# Charger_Board_2.net
KiCad netlist of a schematic drawn in EAGLE
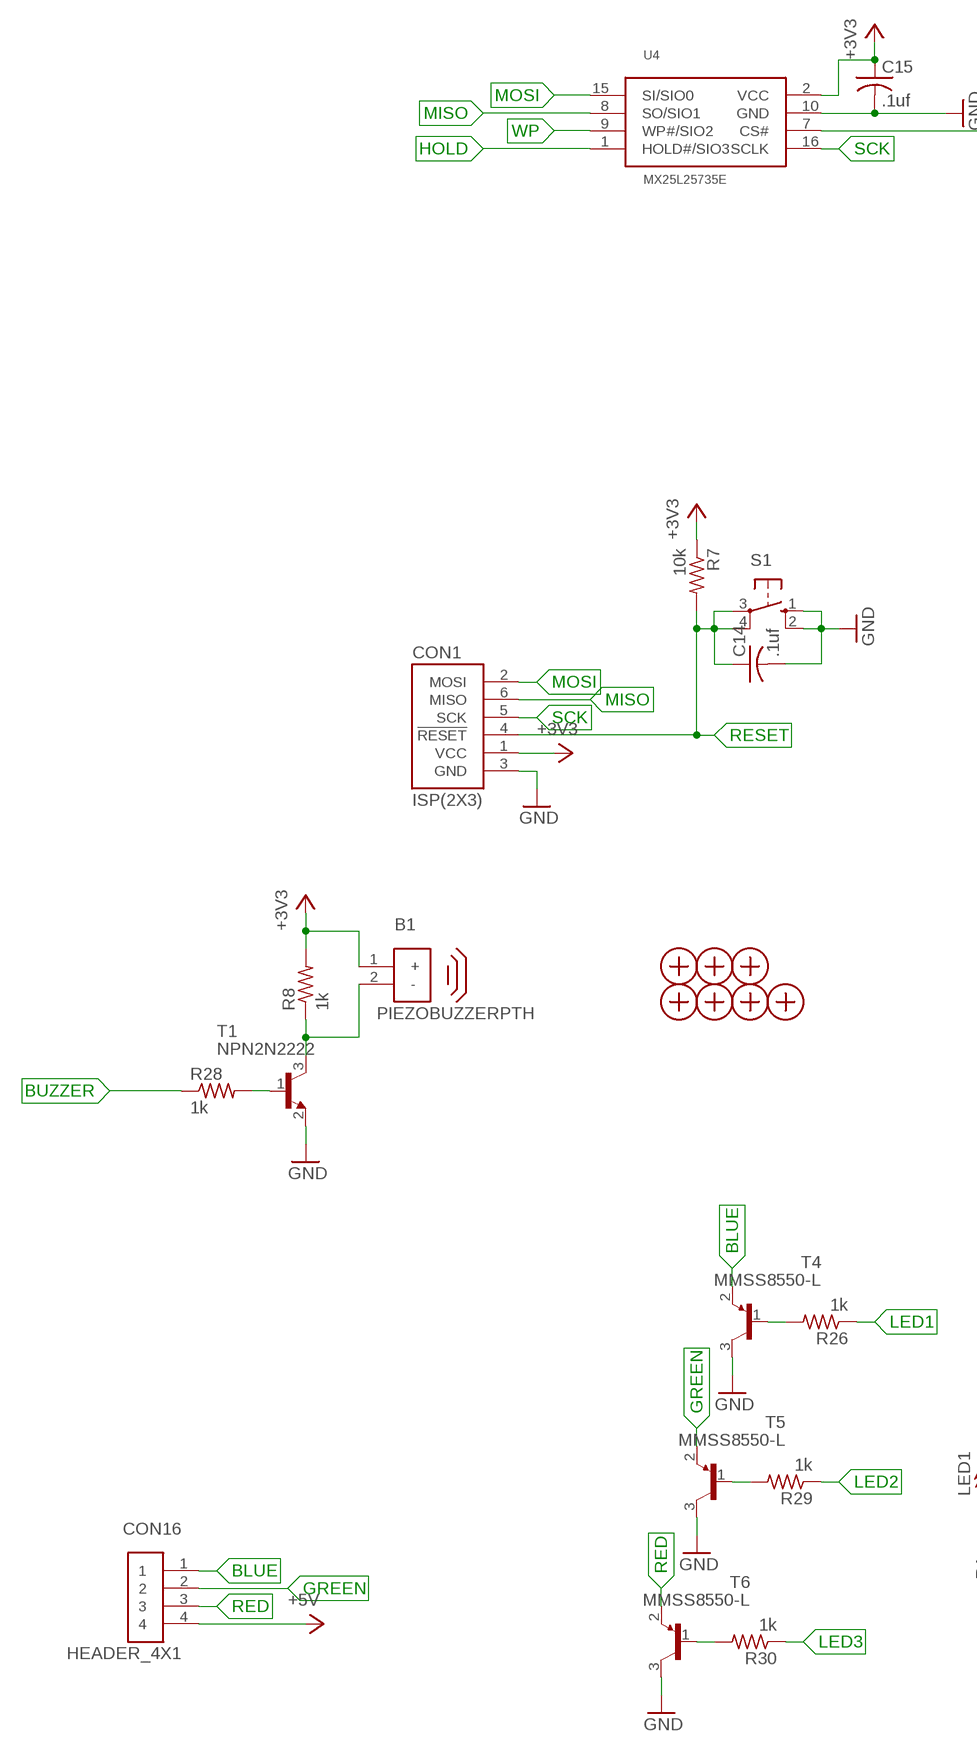
[diagram p0: schematic, sheet 1, part 1 of 2]
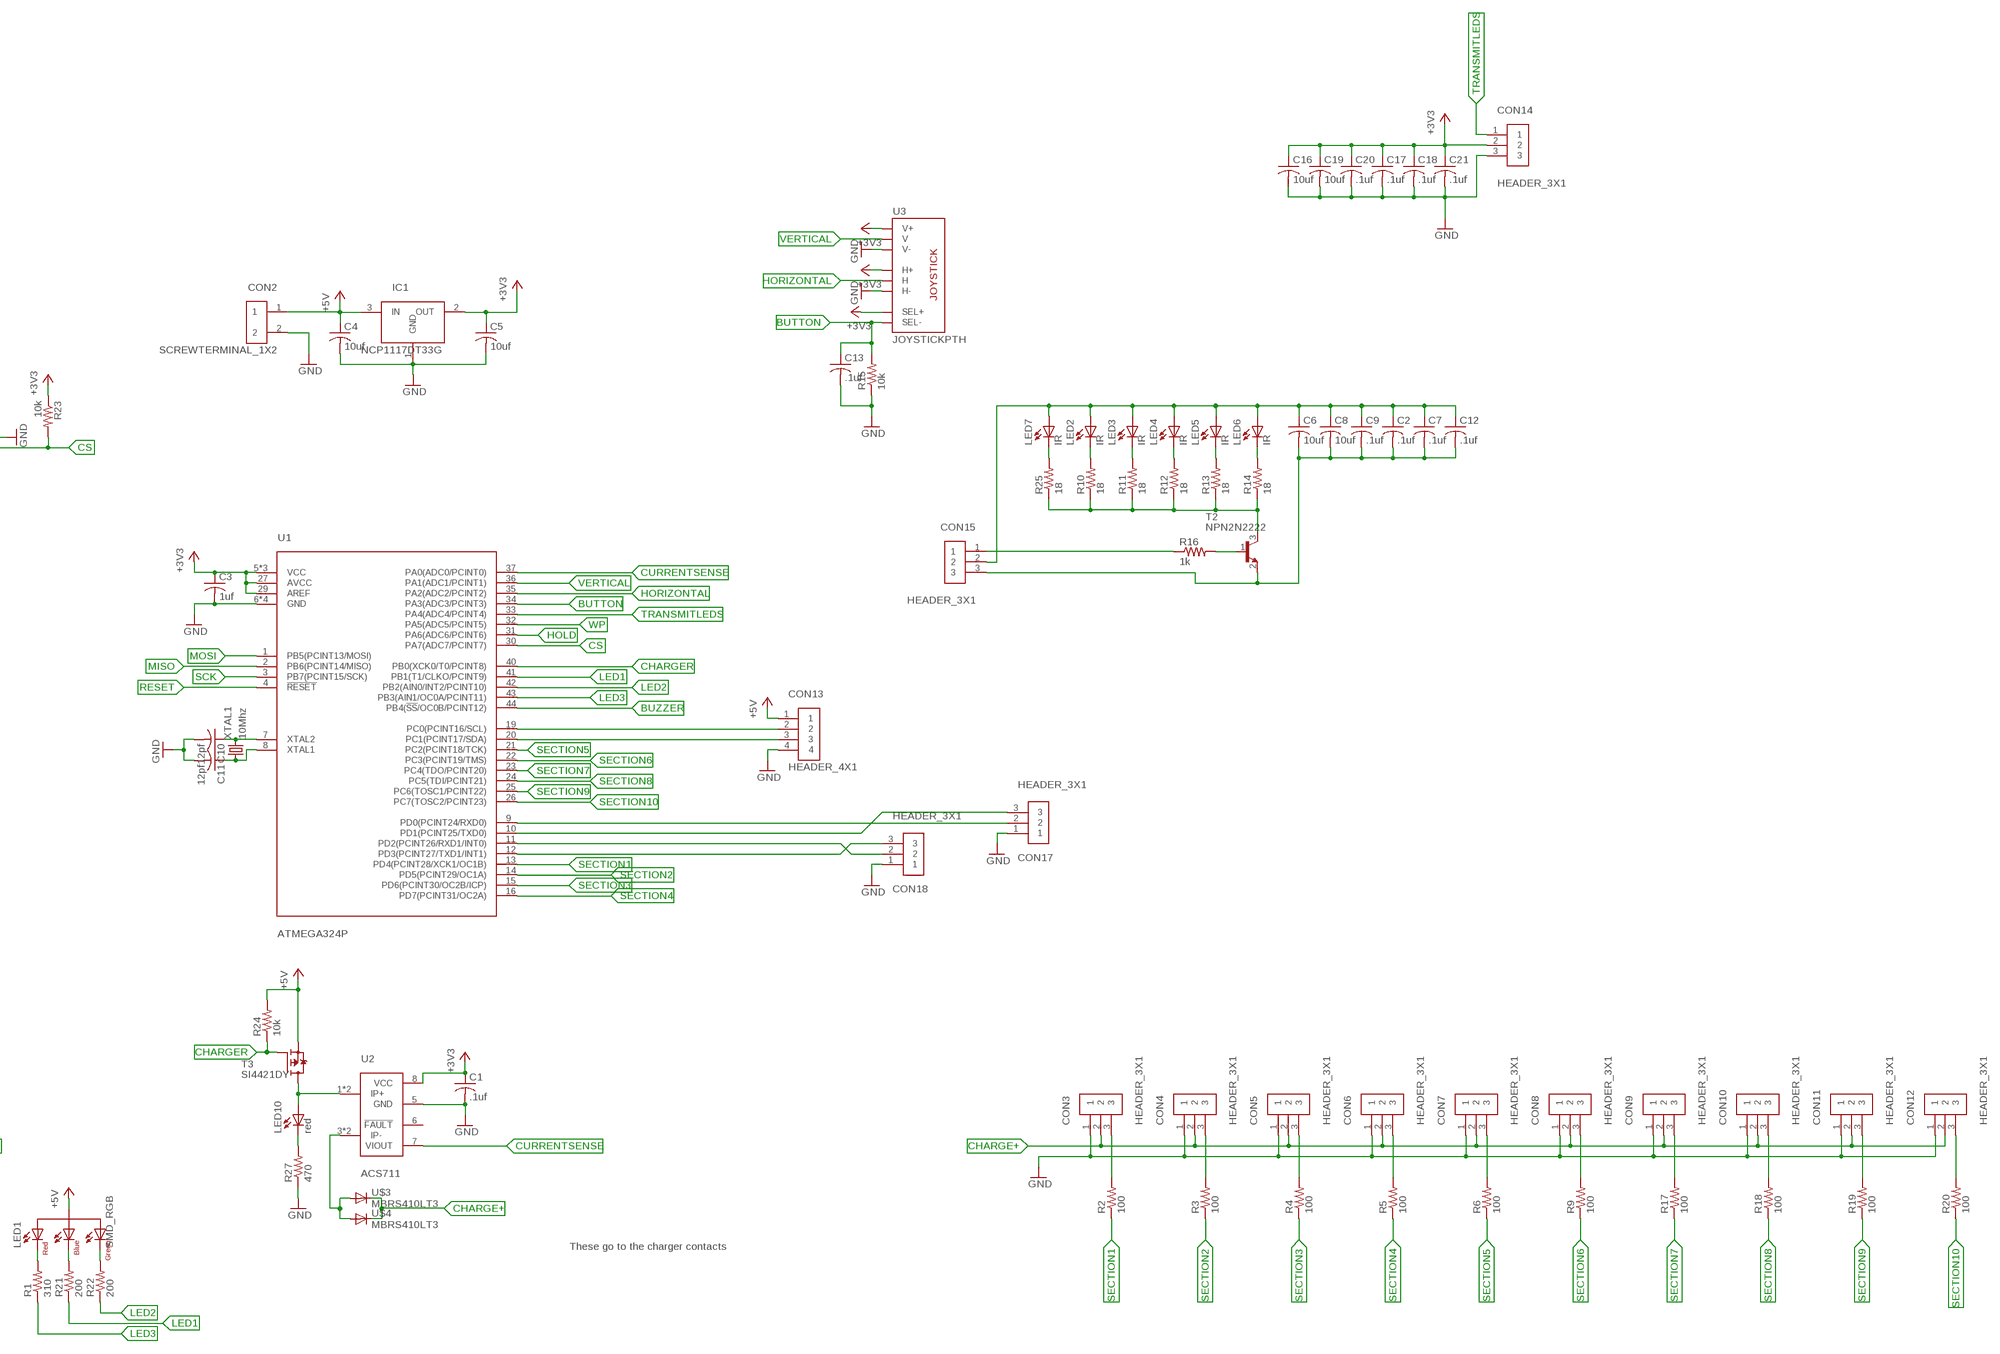
[diagram p1: schematic, sheet 1, part 2 of 2]

(export (version "E")
  (design (tool "Eeschema 10.0.6"))
  (components
    (comp (ref "B1")
      (value "PIEZOBUZZERPTH")
      (footprint "eagle-import:PIEZOBUZZER")
      (libsource (lib "eagle-import") (part "PIEZOBUZZERPTH"))
    )
    (comp (ref "C1")
      (value ".1uf")
      (footprint "eagle-import:0603")
      (libsource (lib "eagle-import") (part "CAP0603"))
    )
    (comp (ref "C2")
      (value ".1uf")
      (footprint "eagle-import:0603")
      (libsource (lib "eagle-import") (part "CAP0603"))
    )
    (comp (ref "C3")
      (value "1uf")
      (footprint "eagle-import:0603")
      (libsource (lib "eagle-import") (part "CAP0603"))
    )
    (comp (ref "C4")
      (value "10uf")
      (footprint "eagle-import:0805")
      (libsource (lib "eagle-import") (part "CAP0805"))
    )
    (comp (ref "C5")
      (value "10uf")
      (footprint "eagle-import:0805")
      (libsource (lib "eagle-import") (part "CAP0805"))
    )
    (comp (ref "C6")
      (value "10uf")
      (footprint "eagle-import:0805")
      (libsource (lib "eagle-import") (part "CAP0805"))
    )
    (comp (ref "C7")
      (value ".1uf")
      (footprint "eagle-import:0603")
      (libsource (lib "eagle-import") (part "CAP0603"))
    )
    (comp (ref "C8")
      (value "10uf")
      (footprint "eagle-import:0805")
      (libsource (lib "eagle-import") (part "CAP0805"))
    )
    (comp (ref "C9")
      (value ".1uf")
      (footprint "eagle-import:0603")
      (libsource (lib "eagle-import") (part "CAP0603"))
    )
    (comp (ref "C10")
      (value "12pf")
      (footprint "eagle-import:0603")
      (libsource (lib "eagle-import") (part "CAP0603"))
    )
    (comp (ref "C11")
      (value "12pf")
      (footprint "eagle-import:0603")
      (libsource (lib "eagle-import") (part "CAP0603"))
    )
    (comp (ref "C12")
      (value ".1uf")
      (footprint "eagle-import:0603")
      (libsource (lib "eagle-import") (part "CAP0603"))
    )
    (comp (ref "C13")
      (value ".1uf")
      (footprint "eagle-import:0603")
      (libsource (lib "eagle-import") (part "CAP0603"))
    )
    (comp (ref "C14")
      (value ".1uf")
      (footprint "eagle-import:0603")
      (libsource (lib "eagle-import") (part "CAP0603"))
    )
    (comp (ref "C15")
      (value ".1uf")
      (footprint "eagle-import:0603")
      (libsource (lib "eagle-import") (part "CAP0603"))
    )
    (comp (ref "C16")
      (value "10uf")
      (footprint "eagle-import:0805")
      (libsource (lib "eagle-import") (part "CAP0805"))
    )
    (comp (ref "C17")
      (value ".1uf")
      (footprint "eagle-import:0603")
      (libsource (lib "eagle-import") (part "CAP0603"))
    )
    (comp (ref "C18")
      (value ".1uf")
      (footprint "eagle-import:0603")
      (libsource (lib "eagle-import") (part "CAP0603"))
    )
    (comp (ref "C19")
      (value "10uf")
      (footprint "eagle-import:0805")
      (libsource (lib "eagle-import") (part "CAP0805"))
    )
    (comp (ref "C20")
      (value ".1uf")
      (footprint "eagle-import:0603")
      (libsource (lib "eagle-import") (part "CAP0603"))
    )
    (comp (ref "C21")
      (value ".1uf")
      (footprint "eagle-import:0603")
      (libsource (lib "eagle-import") (part "CAP0603"))
    )
    (comp (ref "CON1")
      (value "ISP(2X3)")
      (footprint "eagle-import:PINHEADER(2X3)")
      (libsource (lib "eagle-import") (part "ISP(2X3)"))
    )
    (comp (ref "CON2")
      (value "SCREWTERMINAL_1X2")
      (footprint "eagle-import:SCREWTERMINAL_1X2")
      (libsource (lib "eagle-import") (part "SCREWTERMINAL_1X2"))
    )
    (comp (ref "CON3")
      (value "HEADER_3X1")
      (footprint "eagle-import:3PINHEADER_.100_")
      (libsource (lib "eagle-import") (part "HEADER_3X1"))
    )
    (comp (ref "CON4")
      (value "HEADER_3X1")
      (footprint "eagle-import:3PINHEADER_.100_")
      (libsource (lib "eagle-import") (part "HEADER_3X1"))
    )
    (comp (ref "CON5")
      (value "HEADER_3X1")
      (footprint "eagle-import:3PINHEADER_.100_")
      (libsource (lib "eagle-import") (part "HEADER_3X1"))
    )
    (comp (ref "CON6")
      (value "HEADER_3X1")
      (footprint "eagle-import:3PINHEADER_.100_")
      (libsource (lib "eagle-import") (part "HEADER_3X1"))
    )
    (comp (ref "CON7")
      (value "HEADER_3X1")
      (footprint "eagle-import:3PINHEADER_.100_")
      (libsource (lib "eagle-import") (part "HEADER_3X1"))
    )
    (comp (ref "CON8")
      (value "HEADER_3X1")
      (footprint "eagle-import:3PINHEADER_.100_")
      (libsource (lib "eagle-import") (part "HEADER_3X1"))
    )
    (comp (ref "CON9")
      (value "HEADER_3X1")
      (footprint "eagle-import:3PINHEADER_.100_")
      (libsource (lib "eagle-import") (part "HEADER_3X1"))
    )
    (comp (ref "CON10")
      (value "HEADER_3X1")
      (footprint "eagle-import:3PINHEADER_.100_")
      (libsource (lib "eagle-import") (part "HEADER_3X1"))
    )
    (comp (ref "CON11")
      (value "HEADER_3X1")
      (footprint "eagle-import:3PINHEADER_.100_")
      (libsource (lib "eagle-import") (part "HEADER_3X1"))
    )
    (comp (ref "CON12")
      (value "HEADER_3X1")
      (footprint "eagle-import:3PINHEADER_.100_")
      (libsource (lib "eagle-import") (part "HEADER_3X1"))
    )
    (comp (ref "CON13")
      (value "HEADER_4X1")
      (footprint "eagle-import:4PINHEADER_.100_")
      (libsource (lib "eagle-import") (part "HEADER_4X1"))
    )
    (comp (ref "CON14")
      (value "HEADER_3X1")
      (footprint "eagle-import:3PINHEADER_.100_")
      (libsource (lib "eagle-import") (part "HEADER_3X1"))
    )
    (comp (ref "CON15")
      (value "HEADER_3X1")
      (footprint "eagle-import:3PINHEADER_.100_")
      (libsource (lib "eagle-import") (part "HEADER_3X1"))
    )
    (comp (ref "CON16")
      (value "HEADER_4X1")
      (footprint "eagle-import:4PINHEADER_.100_")
      (libsource (lib "eagle-import") (part "HEADER_4X1"))
    )
    (comp (ref "CON17")
      (value "HEADER_3X1")
      (footprint "eagle-import:3PINHEADER_.100_")
      (libsource (lib "eagle-import") (part "HEADER_3X1"))
    )
    (comp (ref "CON18")
      (value "HEADER_3X1")
      (footprint "eagle-import:3PINHEADER_.100_")
      (libsource (lib "eagle-import") (part "HEADER_3X1"))
    )
    (comp (ref "H1")
      (value "MOUNTINGHOLE")
      (footprint "eagle-import:MOUNTINGHOLE")
      (libsource (lib "eagle-import") (part "MOUNTINGHOLE"))
    )
    (comp (ref "H2")
      (value "MOUNTINGHOLE")
      (footprint "eagle-import:MOUNTINGHOLE")
      (libsource (lib "eagle-import") (part "MOUNTINGHOLE"))
    )
    (comp (ref "H3")
      (value "MOUNTINGHOLE")
      (footprint "eagle-import:MOUNTINGHOLE")
      (libsource (lib "eagle-import") (part "MOUNTINGHOLE"))
    )
    (comp (ref "H4")
      (value "MOUNTINGHOLE")
      (footprint "eagle-import:MOUNTINGHOLE")
      (libsource (lib "eagle-import") (part "MOUNTINGHOLE"))
    )
    (comp (ref "H5")
      (value "MOUNTINGHOLE")
      (footprint "eagle-import:MOUNTINGHOLE")
      (libsource (lib "eagle-import") (part "MOUNTINGHOLE"))
    )
    (comp (ref "H6")
      (value "MOUNTINGHOLE")
      (footprint "eagle-import:MOUNTINGHOLE")
      (libsource (lib "eagle-import") (part "MOUNTINGHOLE"))
    )
    (comp (ref "H7")
      (value "MOUNTINGHOLE")
      (footprint "eagle-import:MOUNTINGHOLE")
      (libsource (lib "eagle-import") (part "MOUNTINGHOLE"))
    )
    (comp (ref "IC1")
      (value "NCP1117DT33G")
      (footprint "eagle-import:DPAK")
      (libsource (lib "eagle-import") (part "NCP1117DT33G"))
    )
    (comp (ref "LED1")
      (value "SMD_RGB")
      (footprint "eagle-import:PLCC4")
      (libsource (lib "eagle-import") (part "SMD_RGB"))
    )
    (comp (ref "LED2")
      (value "IR")
      (footprint "eagle-import:5MM_LED_RA")
      (libsource (lib "eagle-import") (part "LED5MMRA"))
    )
    (comp (ref "LED3")
      (value "IR")
      (footprint "eagle-import:5MM_LED_RA")
      (libsource (lib "eagle-import") (part "LED5MMRA"))
    )
    (comp (ref "LED4")
      (value "IR")
      (footprint "eagle-import:5MM_LED_RA")
      (libsource (lib "eagle-import") (part "LED5MMRA"))
    )
    (comp (ref "LED5")
      (value "IR")
      (footprint "eagle-import:5MM_LED_RA")
      (libsource (lib "eagle-import") (part "LED5MMRA"))
    )
    (comp (ref "LED6")
      (value "IR")
      (footprint "eagle-import:5MM_LED_RA")
      (libsource (lib "eagle-import") (part "LED5MMRA"))
    )
    (comp (ref "LED7")
      (value "IR")
      (footprint "eagle-import:5MM_LED_RA")
      (libsource (lib "eagle-import") (part "LED5MMRA"))
    )
    (comp (ref "LED10")
      (value "red")
      (footprint "eagle-import:LED0603")
      (libsource (lib "eagle-import") (part "LED0603"))
    )
    (comp (ref "R1")
      (value "310")
      (footprint "eagle-import:0603")
      (libsource (lib "eagle-import") (part "RES0603"))
    )
    (comp (ref "R2")
      (value "100")
      (footprint "eagle-import:0603")
      (libsource (lib "eagle-import") (part "RES0603"))
    )
    (comp (ref "R3")
      (value "100")
      (footprint "eagle-import:0603")
      (libsource (lib "eagle-import") (part "RES0603"))
    )
    (comp (ref "R4")
      (value "100")
      (footprint "eagle-import:0603")
      (libsource (lib "eagle-import") (part "RES0603"))
    )
    (comp (ref "R5")
      (value "100")
      (footprint "eagle-import:0603")
      (libsource (lib "eagle-import") (part "RES0603"))
    )
    (comp (ref "R6")
      (value "100")
      (footprint "eagle-import:0603")
      (libsource (lib "eagle-import") (part "RES0603"))
    )
    (comp (ref "R7")
      (value "10k")
      (footprint "eagle-import:0603")
      (libsource (lib "eagle-import") (part "RES0603"))
    )
    (comp (ref "R8")
      (value "1k")
      (footprint "eagle-import:0603")
      (libsource (lib "eagle-import") (part "RES0603"))
    )
    (comp (ref "R9")
      (value "100")
      (footprint "eagle-import:0603")
      (libsource (lib "eagle-import") (part "RES0603"))
    )
    (comp (ref "R10")
      (value "18")
      (footprint "eagle-import:0603")
      (libsource (lib "eagle-import") (part "RES0603"))
    )
    (comp (ref "R11")
      (value "18")
      (footprint "eagle-import:0603")
      (libsource (lib "eagle-import") (part "RES0603"))
    )
    (comp (ref "R12")
      (value "18")
      (footprint "eagle-import:0603")
      (libsource (lib "eagle-import") (part "RES0603"))
    )
    (comp (ref "R13")
      (value "18")
      (footprint "eagle-import:0603")
      (libsource (lib "eagle-import") (part "RES0603"))
    )
    (comp (ref "R14")
      (value "18")
      (footprint "eagle-import:0603")
      (libsource (lib "eagle-import") (part "RES0603"))
    )
    (comp (ref "R15")
      (value "10k")
      (footprint "eagle-import:0603")
      (libsource (lib "eagle-import") (part "RES0603"))
    )
    (comp (ref "R16")
      (value "1k")
      (footprint "eagle-import:0603")
      (libsource (lib "eagle-import") (part "RES0603"))
    )
    (comp (ref "R17")
      (value "100")
      (footprint "eagle-import:0603")
      (libsource (lib "eagle-import") (part "RES0603"))
    )
    (comp (ref "R18")
      (value "100")
      (footprint "eagle-import:0603")
      (libsource (lib "eagle-import") (part "RES0603"))
    )
    (comp (ref "R19")
      (value "100")
      (footprint "eagle-import:0603")
      (libsource (lib "eagle-import") (part "RES0603"))
    )
    (comp (ref "R20")
      (value "100")
      (footprint "eagle-import:0603")
      (libsource (lib "eagle-import") (part "RES0603"))
    )
    (comp (ref "R21")
      (value "200")
      (footprint "eagle-import:0603")
      (libsource (lib "eagle-import") (part "RES0603"))
    )
    (comp (ref "R22")
      (value "200")
      (footprint "eagle-import:0603")
      (libsource (lib "eagle-import") (part "RES0603"))
    )
    (comp (ref "R23")
      (value "10k")
      (footprint "eagle-import:0603")
      (libsource (lib "eagle-import") (part "RES0603"))
    )
    (comp (ref "R24")
      (value "10k")
      (footprint "eagle-import:0603")
      (libsource (lib "eagle-import") (part "RES0603"))
    )
    (comp (ref "R25")
      (value "18")
      (footprint "eagle-import:0603")
      (libsource (lib "eagle-import") (part "RES0603"))
    )
    (comp (ref "R26")
      (value "1k")
      (footprint "eagle-import:0603")
      (libsource (lib "eagle-import") (part "RES0603"))
    )
    (comp (ref "R27")
      (value "470")
      (footprint "eagle-import:0603")
      (libsource (lib "eagle-import") (part "RES0603"))
    )
    (comp (ref "R28")
      (value "1k")
      (footprint "eagle-import:0603")
      (libsource (lib "eagle-import") (part "RES0603"))
    )
    (comp (ref "R29")
      (value "1k")
      (footprint "eagle-import:0603")
      (libsource (lib "eagle-import") (part "RES0603"))
    )
    (comp (ref "R30")
      (value "1k")
      (footprint "eagle-import:0603")
      (libsource (lib "eagle-import") (part "RES0603"))
    )
    (comp (ref "S1")
      (value "10-XX")
      (footprint "eagle-import:B3F-10XX")
      (fields (field (name "MPN") "B3F-1000"))
      (libsource (lib "eagle-import") (part "10-XX"))
    )
    (comp (ref "T1")
      (value "NPN2N2222")
      (footprint "eagle-import:SOT23")
      (libsource (lib "eagle-import") (part "NPN2N2222"))
    )
    (comp (ref "T2")
      (value "NPN2N2222")
      (footprint "eagle-import:SOT23")
      (libsource (lib "eagle-import") (part "NPN2N2222"))
    )
    (comp (ref "T3")
      (value "SI4421DY")
      (footprint "eagle-import:S0-8")
      (libsource (lib "eagle-import") (part "SI4421DY"))
    )
    (comp (ref "T4")
      (value "MMSS8550-L")
      (footprint "eagle-import:SOT23")
      (libsource (lib "eagle-import") (part "MMSS8550-L"))
    )
    (comp (ref "T5")
      (value "MMSS8550-L")
      (footprint "eagle-import:SOT23")
      (libsource (lib "eagle-import") (part "MMSS8550-L"))
    )
    (comp (ref "T6")
      (value "MMSS8550-L")
      (footprint "eagle-import:SOT23")
      (libsource (lib "eagle-import") (part "MMSS8550-L"))
    )
    (comp (ref "U$3")
      (value "MBRS410LT3")
      (footprint "eagle-import:SMD_DIODE")
      (libsource (lib "eagle-import") (part "MBRS410LT3"))
    )
    (comp (ref "U$4")
      (value "MBRS410LT3")
      (footprint "eagle-import:SMD_DIODE")
      (libsource (lib "eagle-import") (part "MBRS410LT3"))
    )
    (comp (ref "U1")
      (value "ATMEGA324P")
      (footprint "eagle-import:TQFP44")
      (libsource (lib "eagle-import") (part "ATMEGA324P"))
    )
    (comp (ref "U2")
      (value "ACS711")
      (footprint "eagle-import:8SOIC")
      (libsource (lib "eagle-import") (part "ACS711"))
    )
    (comp (ref "U3")
      (value "JOYSTICKPTH")
      (footprint "eagle-import:JOYSTICK")
      (libsource (lib "eagle-import") (part "JOYSTICKPTH"))
    )
    (comp (ref "U4")
      (value "MX25L25735E")
      (footprint "eagle-import:SOIC16R")
      (libsource (lib "eagle-import") (part "MX25L25735E"))
    )
    (comp (ref "XTAL1")
      (value "10Mhz")
      (footprint "eagle-import:SMDXTAL")
      (libsource (lib "eagle-import") (part "NX5032GA-10.000000MHZ"))
    )
  )
  (nets
    (net (code "1") (name "+3V3") (class "Default")
      (node (ref "B1") (pin "1") (pinfunction "+_1") (pintype "bidirectional"))
      (node (ref "C1") (pin "1") (pinfunction "1_1") (pintype "passive"))
      (node (ref "C15") (pin "1") (pinfunction "1_1") (pintype "passive"))
      (node (ref "C16") (pin "1") (pinfunction "1_1") (pintype "passive"))
      (node (ref "C17") (pin "1") (pinfunction "1_1") (pintype "passive"))
      (node (ref "C18") (pin "1") (pinfunction "1_1") (pintype "passive"))
      (node (ref "C19") (pin "1") (pinfunction "1_1") (pintype "passive"))
      (node (ref "C20") (pin "1") (pinfunction "1_1") (pintype "passive"))
      (node (ref "C21") (pin "1") (pinfunction "1_1") (pintype "passive"))
      (node (ref "C3") (pin "1") (pinfunction "1_1") (pintype "passive"))
      (node (ref "C5") (pin "1") (pinfunction "1_1") (pintype "passive"))
      (node (ref "CON1") (pin "1") (pinfunction "VCC_1") (pintype "bidirectional"))
      (node (ref "CON14") (pin "2") (pinfunction "2_2") (pintype "bidirectional"))
      (node (ref "IC1") (pin "2") (pinfunction "OUT_2") (pintype "bidirectional"))
      (node (ref "R23") (pin "1") (pinfunction "1_1") (pintype "passive"))
      (node (ref "R7") (pin "1") (pinfunction "1_1") (pintype "passive"))
      (node (ref "R8") (pin "2") (pinfunction "2_2") (pintype "passive"))
      (node (ref "U1") (pin "17") (pinfunction "VCC_17") (pintype "bidirectional"))
      (node (ref "U1") (pin "27") (pinfunction "AVCC_27") (pintype "bidirectional"))
      (node (ref "U1") (pin "29") (pinfunction "AREF_29") (pintype "bidirectional"))
      (node (ref "U1") (pin "38") (pinfunction "VCC_38") (pintype "bidirectional"))
      (node (ref "U1") (pin "5") (pinfunction "VCC_5") (pintype "bidirectional"))
      (node (ref "U2") (pin "8") (pinfunction "VCC_8") (pintype "bidirectional"))
      (node (ref "U3") (pin "B1A") (pinfunction "SEL+_B1A") (pintype "bidirectional"))
      (node (ref "U3") (pin "H1") (pinfunction "H+_H1") (pintype "bidirectional"))
      (node (ref "U3") (pin "V1") (pinfunction "V+_V1") (pintype "bidirectional"))
      (node (ref "U4") (pin "2") (pinfunction "VCC_2") (pintype "bidirectional"))
    )
    (net (code "2") (name "+5V") (class "Default")
      (node (ref "C4") (pin "1") (pinfunction "1_1") (pintype "passive"))
      (node (ref "CON13") (pin "1") (pinfunction "1_1") (pintype "bidirectional"))
      (node (ref "CON16") (pin "4") (pinfunction "4_4") (pintype "bidirectional"))
      (node (ref "CON2") (pin "1") (pinfunction "1_1") (pintype "bidirectional"))
      (node (ref "IC1") (pin "3") (pinfunction "IN_3") (pintype "bidirectional"))
      (node (ref "LED1") (pin "2") (pinfunction "COMMONANODE_2") (pintype "passive"))
      (node (ref "R24") (pin "2") (pinfunction "2_2") (pintype "passive"))
      (node (ref "T3") (pin "1") (pinfunction "S_1") (pintype "passive"))
      (node (ref "T3") (pin "2") (pinfunction "S_2") (pintype "passive"))
      (node (ref "T3") (pin "3") (pinfunction "S_3") (pintype "passive"))
    )
    (net (code "3") (name "BLUE") (class "Default")
      (node (ref "CON16") (pin "1") (pinfunction "1_1") (pintype "bidirectional"))
      (node (ref "T4") (pin "2") (pinfunction "E_2") (pintype "passive"))
    )
    (net (code "4") (name "BUTTON") (class "Default")
      (node (ref "C13") (pin "1") (pinfunction "1_1") (pintype "passive"))
      (node (ref "R15") (pin "2") (pinfunction "2_2") (pintype "passive"))
      (node (ref "U1") (pin "34") (pinfunction "PA3(ADC3/PCINT3)_34") (pintype "bidirectional"))
      (node (ref "U3") (pin "B2A") (pinfunction "SEL-_B2A") (pintype "bidirectional"))
    )
    (net (code "5") (name "BUZZER") (class "Default")
      (node (ref "R28") (pin "1") (pinfunction "1_1") (pintype "passive"))
      (node (ref "U1") (pin "44") (pinfunction "PB4(~{SS}/OC0B/PCINT12)_44") (pintype "bidirectional"))
    )
    (net (code "6") (name "CHARGE+") (class "Default")
      (node (ref "CON10") (pin "2") (pinfunction "2_2") (pintype "bidirectional"))
      (node (ref "CON11") (pin "2") (pinfunction "2_2") (pintype "bidirectional"))
      (node (ref "CON12") (pin "2") (pinfunction "2_2") (pintype "bidirectional"))
      (node (ref "CON3") (pin "2") (pinfunction "2_2") (pintype "bidirectional"))
      (node (ref "CON4") (pin "2") (pinfunction "2_2") (pintype "bidirectional"))
      (node (ref "CON5") (pin "2") (pinfunction "2_2") (pintype "bidirectional"))
      (node (ref "CON6") (pin "2") (pinfunction "2_2") (pintype "bidirectional"))
      (node (ref "CON7") (pin "2") (pinfunction "2_2") (pintype "bidirectional"))
      (node (ref "CON8") (pin "2") (pinfunction "2_2") (pintype "bidirectional"))
      (node (ref "CON9") (pin "2") (pinfunction "2_2") (pintype "bidirectional"))
      (node (ref "U$3") (pin "2") (pinfunction "C_2") (pintype "passive"))
      (node (ref "U$4") (pin "2") (pinfunction "C_2") (pintype "passive"))
    )
    (net (code "7") (name "CHARGER") (class "Default")
      (node (ref "R24") (pin "1") (pinfunction "1_1") (pintype "passive"))
      (node (ref "T3") (pin "4") (pinfunction "G_4") (pintype "passive"))
      (node (ref "U1") (pin "40") (pinfunction "PB0(XCK0/T0/PCINT8)_40") (pintype "bidirectional"))
    )
    (net (code "8") (name "CS") (class "Default")
      (node (ref "R23") (pin "2") (pinfunction "2_2") (pintype "passive"))
      (node (ref "U1") (pin "30") (pinfunction "PA7(ADC7/PCINT7)_30") (pintype "bidirectional"))
      (node (ref "U4") (pin "7") (pinfunction "CS#_7") (pintype "bidirectional"))
    )
    (net (code "9") (name "CURRENTSENSE") (class "Default")
      (node (ref "U1") (pin "37") (pinfunction "PA0(ADC0/PCINT0)_37") (pintype "bidirectional"))
      (node (ref "U2") (pin "7") (pinfunction "VIOUT_7") (pintype "bidirectional"))
    )
    (net (code "10") (name "GND") (class "Default")
      (node (ref "C1") (pin "2") (pinfunction "2_2") (pintype "passive"))
      (node (ref "C10") (pin "2") (pinfunction "2_2") (pintype "passive"))
      (node (ref "C11") (pin "2") (pinfunction "2_2") (pintype "passive"))
      (node (ref "C13") (pin "2") (pinfunction "2_2") (pintype "passive"))
      (node (ref "C14") (pin "2") (pinfunction "2_2") (pintype "passive"))
      (node (ref "C15") (pin "2") (pinfunction "2_2") (pintype "passive"))
      (node (ref "C16") (pin "2") (pinfunction "2_2") (pintype "passive"))
      (node (ref "C17") (pin "2") (pinfunction "2_2") (pintype "passive"))
      (node (ref "C18") (pin "2") (pinfunction "2_2") (pintype "passive"))
      (node (ref "C19") (pin "2") (pinfunction "2_2") (pintype "passive"))
      (node (ref "C20") (pin "2") (pinfunction "2_2") (pintype "passive"))
      (node (ref "C21") (pin "2") (pinfunction "2_2") (pintype "passive"))
      (node (ref "C3") (pin "2") (pinfunction "2_2") (pintype "passive"))
      (node (ref "C4") (pin "2") (pinfunction "2_2") (pintype "passive"))
      (node (ref "C5") (pin "2") (pinfunction "2_2") (pintype "passive"))
      (node (ref "CON1") (pin "3") (pinfunction "GND_3") (pintype "bidirectional"))
      (node (ref "CON10") (pin "1") (pinfunction "1_1") (pintype "bidirectional"))
      (node (ref "CON11") (pin "1") (pinfunction "1_1") (pintype "bidirectional"))
      (node (ref "CON12") (pin "1") (pinfunction "1_1") (pintype "bidirectional"))
      (node (ref "CON13") (pin "4") (pinfunction "4_4") (pintype "bidirectional"))
      (node (ref "CON14") (pin "3") (pinfunction "3_3") (pintype "bidirectional"))
      (node (ref "CON17") (pin "1") (pinfunction "1_1") (pintype "bidirectional"))
      (node (ref "CON18") (pin "1") (pinfunction "1_1") (pintype "bidirectional"))
      (node (ref "CON2") (pin "2") (pinfunction "2_2") (pintype "bidirectional"))
      (node (ref "CON3") (pin "1") (pinfunction "1_1") (pintype "bidirectional"))
      (node (ref "CON4") (pin "1") (pinfunction "1_1") (pintype "bidirectional"))
      (node (ref "CON5") (pin "1") (pinfunction "1_1") (pintype "bidirectional"))
      (node (ref "CON6") (pin "1") (pinfunction "1_1") (pintype "bidirectional"))
      (node (ref "CON7") (pin "1") (pinfunction "1_1") (pintype "bidirectional"))
      (node (ref "CON8") (pin "1") (pinfunction "1_1") (pintype "bidirectional"))
      (node (ref "CON9") (pin "1") (pinfunction "1_1") (pintype "bidirectional"))
      (node (ref "IC1") (pin "1") (pinfunction "GND_1") (pintype "bidirectional"))
      (node (ref "R15") (pin "1") (pinfunction "1_1") (pintype "passive"))
      (node (ref "R27") (pin "1") (pinfunction "1_1") (pintype "passive"))
      (node (ref "S1") (pin "1") (pinfunction "S_1") (pintype "passive"))
      (node (ref "S1") (pin "2") (pinfunction "S1_2") (pintype "passive"))
      (node (ref "T1") (pin "2") (pinfunction "E_2") (pintype "passive"))
      (node (ref "T4") (pin "3") (pinfunction "C_3") (pintype "passive"))
      (node (ref "T5") (pin "3") (pinfunction "C_3") (pintype "passive"))
      (node (ref "T6") (pin "3") (pinfunction "C_3") (pintype "passive"))
      (node (ref "U1") (pin "18") (pinfunction "GND_18") (pintype "bidirectional"))
      (node (ref "U1") (pin "28") (pinfunction "GND_28") (pintype "bidirectional"))
      (node (ref "U1") (pin "39") (pinfunction "GND_39") (pintype "bidirectional"))
      (node (ref "U1") (pin "6") (pinfunction "GND_6") (pintype "bidirectional"))
      (node (ref "U2") (pin "5") (pinfunction "GND_5") (pintype "bidirectional"))
      (node (ref "U3") (pin "H3") (pinfunction "H-_H3") (pintype "bidirectional"))
      (node (ref "U3") (pin "V3") (pinfunction "V-_V3") (pintype "bidirectional"))
      (node (ref "U4") (pin "10") (pinfunction "GND_10") (pintype "bidirectional"))
    )
    (net (code "11") (name "GREEN") (class "Default")
      (node (ref "CON16") (pin "2") (pinfunction "2_2") (pintype "bidirectional"))
      (node (ref "T5") (pin "2") (pinfunction "E_2") (pintype "passive"))
    )
    (net (code "12") (name "HOLD") (class "Default")
      (node (ref "U1") (pin "31") (pinfunction "PA6(ADC6/PCINT6)_31") (pintype "bidirectional"))
      (node (ref "U4") (pin "1") (pinfunction "HOLD#/SIO3_1") (pintype "bidirectional"))
    )
    (net (code "13") (name "HORIZONTAL") (class "Default")
      (node (ref "U1") (pin "35") (pinfunction "PA2(ADC2/PCINT2)_35") (pintype "bidirectional"))
      (node (ref "U3") (pin "H2") (pinfunction "H_H2") (pintype "bidirectional"))
    )
    (net (code "14") (name "LED1") (class "Default")
      (node (ref "R21") (pin "1") (pinfunction "1_1") (pintype "passive"))
      (node (ref "R26") (pin "1") (pinfunction "1_1") (pintype "passive"))
      (node (ref "U1") (pin "41") (pinfunction "PB1(T1/CLKO/PCINT9)_41") (pintype "bidirectional"))
    )
    (net (code "15") (name "LED2") (class "Default")
      (node (ref "R22") (pin "1") (pinfunction "1_1") (pintype "passive"))
      (node (ref "R29") (pin "1") (pinfunction "1_1") (pintype "passive"))
      (node (ref "U1") (pin "42") (pinfunction "PB2(AIN0/INT2/PCINT10)_42") (pintype "bidirectional"))
    )
    (net (code "16") (name "LED3") (class "Default")
      (node (ref "R1") (pin "1") (pinfunction "1_1") (pintype "passive"))
      (node (ref "R30") (pin "1") (pinfunction "1_1") (pintype "passive"))
      (node (ref "U1") (pin "43") (pinfunction "PB3(AIN1/OC0A/PCINT11)_43") (pintype "bidirectional"))
    )
    (net (code "17") (name "MISO") (class "Default")
      (node (ref "CON1") (pin "6") (pinfunction "MISO_6") (pintype "bidirectional"))
      (node (ref "U1") (pin "2") (pinfunction "PB6(PCINT14/MISO)_2") (pintype "bidirectional"))
      (node (ref "U4") (pin "8") (pinfunction "SO/SIO1_8") (pintype "bidirectional"))
    )
    (net (code "18") (name "MOSI") (class "Default")
      (node (ref "CON1") (pin "2") (pinfunction "MOSI_2") (pintype "bidirectional"))
      (node (ref "U1") (pin "1") (pinfunction "PB5(PCINT13/MOSI)_1") (pintype "bidirectional"))
      (node (ref "U4") (pin "15") (pinfunction "SI/SIO0_15") (pintype "bidirectional"))
    )
    (net (code "19") (name "Net-(B1--)") (class "Default")
      (node (ref "B1") (pin "2") (pinfunction "-_2") (pintype "bidirectional"))
      (node (ref "R8") (pin "1") (pinfunction "1_1") (pintype "passive"))
      (node (ref "T1") (pin "3") (pinfunction "C_3") (pintype "passive"))
    )
    (net (code "20") (name "Net-(CON3-Pad3)") (class "Default")
      (node (ref "CON3") (pin "3") (pinfunction "3_3") (pintype "bidirectional"))
      (node (ref "R2") (pin "2") (pinfunction "2_2") (pintype "passive"))
    )
    (net (code "21") (name "Net-(CON4-Pad3)") (class "Default")
      (node (ref "CON4") (pin "3") (pinfunction "3_3") (pintype "bidirectional"))
      (node (ref "R3") (pin "2") (pinfunction "2_2") (pintype "passive"))
    )
    (net (code "22") (name "Net-(CON5-Pad3)") (class "Default")
      (node (ref "CON5") (pin "3") (pinfunction "3_3") (pintype "bidirectional"))
      (node (ref "R4") (pin "2") (pinfunction "2_2") (pintype "passive"))
    )
    (net (code "23") (name "Net-(CON6-Pad3)") (class "Default")
      (node (ref "CON6") (pin "3") (pinfunction "3_3") (pintype "bidirectional"))
      (node (ref "R5") (pin "2") (pinfunction "2_2") (pintype "passive"))
    )
    (net (code "24") (name "Net-(CON7-Pad3)") (class "Default")
      (node (ref "CON7") (pin "3") (pinfunction "3_3") (pintype "bidirectional"))
      (node (ref "R6") (pin "2") (pinfunction "2_2") (pintype "passive"))
    )
    (net (code "25") (name "Net-(CON8-Pad3)") (class "Default")
      (node (ref "CON8") (pin "3") (pinfunction "3_3") (pintype "bidirectional"))
      (node (ref "R9") (pin "2") (pinfunction "2_2") (pintype "passive"))
    )
    (net (code "26") (name "Net-(CON9-Pad3)") (class "Default")
      (node (ref "CON9") (pin "3") (pinfunction "3_3") (pintype "bidirectional"))
      (node (ref "R17") (pin "2") (pinfunction "2_2") (pintype "passive"))
    )
    (net (code "27") (name "Net-(CON10-Pad3)") (class "Default")
      (node (ref "CON10") (pin "3") (pinfunction "3_3") (pintype "bidirectional"))
      (node (ref "R18") (pin "2") (pinfunction "2_2") (pintype "passive"))
    )
    (net (code "28") (name "Net-(CON11-Pad3)") (class "Default")
      (node (ref "CON11") (pin "3") (pinfunction "3_3") (pintype "bidirectional"))
      (node (ref "R19") (pin "2") (pinfunction "2_2") (pintype "passive"))
    )
    (net (code "29") (name "Net-(CON12-Pad3)") (class "Default")
      (node (ref "CON12") (pin "3") (pinfunction "3_3") (pintype "bidirectional"))
      (node (ref "R20") (pin "2") (pinfunction "2_2") (pintype "passive"))
    )
    (net (code "30") (name "Net-(CON15-Pad1)") (class "Default")
      (node (ref "CON15") (pin "1") (pinfunction "1_1") (pintype "bidirectional"))
      (node (ref "R16") (pin "1") (pinfunction "1_1") (pintype "passive"))
    )
    (net (code "31") (name "Net-(LED1-BLUECATHODE)") (class "Default")
      (node (ref "LED1") (pin "3") (pinfunction "BLUECATHODE_3") (pintype "passive"))
      (node (ref "R21") (pin "2") (pinfunction "2_2") (pintype "passive"))
    )
    (net (code "32") (name "Net-(LED1-GREENCATHODE)") (class "Default")
      (node (ref "LED1") (pin "4") (pinfunction "GREENCATHODE_4") (pintype "passive"))
      (node (ref "R22") (pin "2") (pinfunction "2_2") (pintype "passive"))
    )
    (net (code "33") (name "Net-(LED1-REDCATHODE)") (class "Default")
      (node (ref "LED1") (pin "1") (pinfunction "REDCATHODE_1") (pintype "passive"))
      (node (ref "R1") (pin "2") (pinfunction "2_2") (pintype "passive"))
    )
    (net (code "34") (name "Net-(LED2-A)") (class "Default")
      (node (ref "C12") (pin "1") (pinfunction "1_1") (pintype "passive"))
      (node (ref "C2") (pin "1") (pinfunction "1_1") (pintype "passive"))
      (node (ref "C6") (pin "1") (pinfunction "1_1") (pintype "passive"))
      (node (ref "C7") (pin "1") (pinfunction "1_1") (pintype "passive"))
      (node (ref "C8") (pin "1") (pinfunction "1_1") (pintype "passive"))
      (node (ref "C9") (pin "1") (pinfunction "1_1") (pintype "passive"))
      (node (ref "CON15") (pin "2") (pinfunction "2_2") (pintype "bidirectional"))
      (node (ref "LED2") (pin "1") (pinfunction "A_1") (pintype "passive"))
      (node (ref "LED3") (pin "1") (pinfunction "A_1") (pintype "passive"))
      (node (ref "LED4") (pin "1") (pinfunction "A_1") (pintype "passive"))
      (node (ref "LED5") (pin "1") (pinfunction "A_1") (pintype "passive"))
      (node (ref "LED6") (pin "1") (pinfunction "A_1") (pintype "passive"))
      (node (ref "LED7") (pin "1") (pinfunction "A_1") (pintype "passive"))
    )
    (net (code "35") (name "Net-(LED2-C)") (class "Default")
      (node (ref "LED2") (pin "2") (pinfunction "C_2") (pintype "passive"))
      (node (ref "R10") (pin "2") (pinfunction "2_2") (pintype "passive"))
    )
    (net (code "36") (name "Net-(LED3-C)") (class "Default")
      (node (ref "LED3") (pin "2") (pinfunction "C_2") (pintype "passive"))
      (node (ref "R11") (pin "2") (pinfunction "2_2") (pintype "passive"))
    )
    (net (code "37") (name "Net-(LED4-C)") (class "Default")
      (node (ref "LED4") (pin "2") (pinfunction "C_2") (pintype "passive"))
      (node (ref "R12") (pin "2") (pinfunction "2_2") (pintype "passive"))
    )
    (net (code "38") (name "Net-(LED5-C)") (class "Default")
      (node (ref "LED5") (pin "2") (pinfunction "C_2") (pintype "passive"))
      (node (ref "R13") (pin "2") (pinfunction "2_2") (pintype "passive"))
    )
    (net (code "39") (name "Net-(LED6-C)") (class "Default")
      (node (ref "LED6") (pin "2") (pinfunction "C_2") (pintype "passive"))
      (node (ref "R14") (pin "2") (pinfunction "2_2") (pintype "passive"))
    )
    (net (code "40") (name "Net-(LED7-C)") (class "Default")
      (node (ref "LED7") (pin "2") (pinfunction "C_2") (pintype "passive"))
      (node (ref "R25") (pin "2") (pinfunction "2_2") (pintype "passive"))
    )
    (net (code "41") (name "Net-(LED10-A)") (class "Default")
      (node (ref "LED10") (pin "2") (pinfunction "A_2") (pintype "passive"))
      (node (ref "T3") (pin "5") (pinfunction "D_5") (pintype "passive"))
      (node (ref "T3") (pin "6") (pinfunction "D_6") (pintype "passive"))
      (node (ref "T3") (pin "7") (pinfunction "D_7") (pintype "passive"))
      (node (ref "T3") (pin "8") (pinfunction "D_8") (pintype "passive"))
      (node (ref "U2") (pin "1") (pinfunction "IP+_1") (pintype "bidirectional"))
      (node (ref "U2") (pin "2") (pinfunction "IP+_2") (pintype "bidirectional"))
    )
    (net (code "42") (name "Net-(LED10-C)") (class "Default")
      (node (ref "LED10") (pin "1") (pinfunction "C_1") (pintype "passive"))
      (node (ref "R27") (pin "2") (pinfunction "2_2") (pintype "passive"))
    )
    (net (code "43") (name "Net-(T1-B)") (class "Default")
      (node (ref "R28") (pin "2") (pinfunction "2_2") (pintype "passive"))
      (node (ref "T1") (pin "1") (pinfunction "B_1") (pintype "passive"))
    )
    (net (code "44") (name "Net-(T2-B)") (class "Default")
      (node (ref "R16") (pin "2") (pinfunction "2_2") (pintype "passive"))
      (node (ref "T2") (pin "1") (pinfunction "B_1") (pintype "passive"))
    )
    (net (code "45") (name "Net-(T2-C)") (class "Default")
      (node (ref "R10") (pin "1") (pinfunction "1_1") (pintype "passive"))
      (node (ref "R11") (pin "1") (pinfunction "1_1") (pintype "passive"))
      (node (ref "R12") (pin "1") (pinfunction "1_1") (pintype "passive"))
      (node (ref "R13") (pin "1") (pinfunction "1_1") (pintype "passive"))
      (node (ref "R14") (pin "1") (pinfunction "1_1") (pintype "passive"))
      (node (ref "R25") (pin "1") (pinfunction "1_1") (pintype "passive"))
      (node (ref "T2") (pin "3") (pinfunction "C_3") (pintype "passive"))
    )
    (net (code "46") (name "Net-(T2-E)") (class "Default")
      (node (ref "C12") (pin "2") (pinfunction "2_2") (pintype "passive"))
      (node (ref "C2") (pin "2") (pinfunction "2_2") (pintype "passive"))
      (node (ref "C6") (pin "2") (pinfunction "2_2") (pintype "passive"))
      (node (ref "C7") (pin "2") (pinfunction "2_2") (pintype "passive"))
      (node (ref "C8") (pin "2") (pinfunction "2_2") (pintype "passive"))
      (node (ref "C9") (pin "2") (pinfunction "2_2") (pintype "passive"))
      (node (ref "CON15") (pin "3") (pinfunction "3_3") (pintype "bidirectional"))
      (node (ref "T2") (pin "2") (pinfunction "E_2") (pintype "passive"))
    )
    (net (code "47") (name "Net-(T4-B)") (class "Default")
      (node (ref "R26") (pin "2") (pinfunction "2_2") (pintype "passive"))
      (node (ref "T4") (pin "1") (pinfunction "B_1") (pintype "passive"))
    )
    (net (code "48") (name "Net-(T5-B)") (class "Default")
      (node (ref "R29") (pin "2") (pinfunction "2_2") (pintype "passive"))
      (node (ref "T5") (pin "1") (pinfunction "B_1") (pintype "passive"))
    )
    (net (code "49") (name "Net-(T6-B)") (class "Default")
      (node (ref "R30") (pin "2") (pinfunction "2_2") (pintype "passive"))
      (node (ref "T6") (pin "1") (pinfunction "B_1") (pintype "passive"))
    )
    (net (code "50") (name "Net-(U$3-A)") (class "Default")
      (node (ref "U$3") (pin "1") (pinfunction "A_1") (pintype "passive"))
      (node (ref "U$4") (pin "1") (pinfunction "A_1") (pintype "passive"))
      (node (ref "U2") (pin "3") (pinfunction "IP-_3") (pintype "bidirectional"))
      (node (ref "U2") (pin "4") (pinfunction "IP-_4") (pintype "bidirectional"))
    )
    (net (code "51") (name "Net-(U1-PC0(PCINT16{slash}SCL))") (class "Default")
      (node (ref "CON13") (pin "2") (pinfunction "2_2") (pintype "bidirectional"))
      (node (ref "U1") (pin "19") (pinfunction "PC0(PCINT16/SCL)_19") (pintype "bidirectional"))
    )
    (net (code "52") (name "Net-(U1-PC1(PCINT17{slash}SDA))") (class "Default")
      (node (ref "CON13") (pin "3") (pinfunction "3_3") (pintype "bidirectional"))
      (node (ref "U1") (pin "20") (pinfunction "PC1(PCINT17/SDA)_20") (pintype "bidirectional"))
    )
    (net (code "53") (name "Net-(U1-PD0(PCINT24{slash}RXD0))") (class "Default")
      (node (ref "CON17") (pin "2") (pinfunction "2_2") (pintype "bidirectional"))
      (node (ref "U1") (pin "9") (pinfunction "PD0(PCINT24/RXD0)_9") (pintype "bidirectional"))
    )
    (net (code "54") (name "Net-(U1-PD1(PCINT25{slash}TXD0))") (class "Default")
      (node (ref "CON17") (pin "3") (pinfunction "3_3") (pintype "bidirectional"))
      (node (ref "U1") (pin "10") (pinfunction "PD1(PCINT25/TXD0)_10") (pintype "bidirectional"))
    )
    (net (code "55") (name "Net-(U1-PD2(PCINT26{slash}RXD1{slash}INT0))") (class "Default")
      (node (ref "CON18") (pin "2") (pinfunction "2_2") (pintype "bidirectional"))
      (node (ref "U1") (pin "11") (pinfunction "PD2(PCINT26/RXD1/INT0)_11") (pintype "bidirectional"))
    )
    (net (code "56") (name "Net-(U1-PD3(PCINT27{slash}TXD1{slash}INT1))") (class "Default")
      (node (ref "CON18") (pin "3") (pinfunction "3_3") (pintype "bidirectional"))
      (node (ref "U1") (pin "12") (pinfunction "PD3(PCINT27/TXD1/INT1)_12") (pintype "bidirectional"))
    )
    (net (code "57") (name "Net-(U1-XTAL1)") (class "Default")
      (node (ref "C11") (pin "1") (pinfunction "1_1") (pintype "passive"))
      (node (ref "U1") (pin "8") (pinfunction "XTAL1_8") (pintype "bidirectional"))
      (node (ref "XTAL1") (pin "1") (pinfunction "1_1") (pintype "passive"))
    )
    (net (code "58") (name "Net-(U1-XTAL2)") (class "Default")
      (node (ref "C10") (pin "1") (pinfunction "1_1") (pintype "passive"))
      (node (ref "U1") (pin "7") (pinfunction "XTAL2_7") (pintype "bidirectional"))
      (node (ref "XTAL1") (pin "2") (pinfunction "2_2") (pintype "passive"))
    )
    (net (code "59") (name "RED") (class "Default")
      (node (ref "CON16") (pin "3") (pinfunction "3_3") (pintype "bidirectional"))
      (node (ref "T6") (pin "2") (pinfunction "E_2") (pintype "passive"))
    )
    (net (code "60") (name "RESET") (class "Default")
      (node (ref "C14") (pin "1") (pinfunction "1_1") (pintype "passive"))
      (node (ref "CON1") (pin "4") (pinfunction "~{RESET}_4") (pintype "bidirectional"))
      (node (ref "R7") (pin "2") (pinfunction "2_2") (pintype "passive"))
      (node (ref "S1") (pin "3") (pinfunction "P_3") (pintype "passive"))
      (node (ref "S1") (pin "4") (pinfunction "P1_4") (pintype "passive"))
      (node (ref "U1") (pin "4") (pinfunction "~{RESET}_4") (pintype "bidirectional"))
    )
    (net (code "61") (name "SCK") (class "Default")
      (node (ref "CON1") (pin "5") (pinfunction "SCK_5") (pintype "bidirectional"))
      (node (ref "U1") (pin "3") (pinfunction "PB7(PCINT15/SCK)_3") (pintype "bidirectional"))
      (node (ref "U4") (pin "16") (pinfunction "SCLK_16") (pintype "bidirectional"))
    )
    (net (code "62") (name "SECTION1") (class "Default")
      (node (ref "R2") (pin "1") (pinfunction "1_1") (pintype "passive"))
      (node (ref "U1") (pin "13") (pinfunction "PD4(PCINT28/XCK1/OC1B)_13") (pintype "bidirectional"))
    )
    (net (code "63") (name "SECTION2") (class "Default")
      (node (ref "R3") (pin "1") (pinfunction "1_1") (pintype "passive"))
      (node (ref "U1") (pin "14") (pinfunction "PD5(PCINT29/OC1A)_14") (pintype "bidirectional"))
    )
    (net (code "64") (name "SECTION3") (class "Default")
      (node (ref "R4") (pin "1") (pinfunction "1_1") (pintype "passive"))
      (node (ref "U1") (pin "15") (pinfunction "PD6(PCINT30/OC2B/ICP)_15") (pintype "bidirectional"))
    )
    (net (code "65") (name "SECTION4") (class "Default")
      (node (ref "R5") (pin "1") (pinfunction "1_1") (pintype "passive"))
      (node (ref "U1") (pin "16") (pinfunction "PD7(PCINT31/OC2A)_16") (pintype "bidirectional"))
    )
    (net (code "66") (name "SECTION5") (class "Default")
      (node (ref "R6") (pin "1") (pinfunction "1_1") (pintype "passive"))
      (node (ref "U1") (pin "21") (pinfunction "PC2(PCINT18/TCK)_21") (pintype "bidirectional"))
    )
    (net (code "67") (name "SECTION6") (class "Default")
      (node (ref "R9") (pin "1") (pinfunction "1_1") (pintype "passive"))
      (node (ref "U1") (pin "22") (pinfunction "PC3(PCINT19/TMS)_22") (pintype "bidirectional"))
    )
    (net (code "68") (name "SECTION7") (class "Default")
      (node (ref "R17") (pin "1") (pinfunction "1_1") (pintype "passive"))
      (node (ref "U1") (pin "23") (pinfunction "PC4(TDO/PCINT20)_23") (pintype "bidirectional"))
    )
    (net (code "69") (name "SECTION8") (class "Default")
      (node (ref "R18") (pin "1") (pinfunction "1_1") (pintype "passive"))
      (node (ref "U1") (pin "24") (pinfunction "PC5(TDI/PCINT21)_24") (pintype "bidirectional"))
    )
    (net (code "70") (name "SECTION9") (class "Default")
      (node (ref "R19") (pin "1") (pinfunction "1_1") (pintype "passive"))
      (node (ref "U1") (pin "25") (pinfunction "PC6(TOSC1/PCINT22)_25") (pintype "bidirectional"))
    )
    (net (code "71") (name "SECTION10") (class "Default")
      (node (ref "R20") (pin "1") (pinfunction "1_1") (pintype "passive"))
      (node (ref "U1") (pin "26") (pinfunction "PC7(TOSC2/PCINT23)_26") (pintype "bidirectional"))
    )
    (net (code "72") (name "TRANSMITLEDS") (class "Default")
      (node (ref "CON14") (pin "1") (pinfunction "1_1") (pintype "bidirectional"))
      (node (ref "U1") (pin "33") (pinfunction "PA4(ADC4/PCINT4)_33") (pintype "bidirectional"))
    )
    (net (code "73") (name "VERTICAL") (class "Default")
      (node (ref "U1") (pin "36") (pinfunction "PA1(ADC1/PCINT1)_36") (pintype "bidirectional"))
      (node (ref "U3") (pin "V2") (pinfunction "V_V2") (pintype "bidirectional"))
    )
    (net (code "74") (name "WP") (class "Default")
      (node (ref "U1") (pin "32") (pinfunction "PA5(ADC5/PCINT5)_32") (pintype "bidirectional"))
      (node (ref "U4") (pin "9") (pinfunction "WP#/SIO2_9") (pintype "bidirectional"))
    )
    (net (code "75") (name "unconnected-(U2-~{FAULT}-Pad6)") (class "Default")
      (node (ref "U2") (pin "6") (pinfunction "~{FAULT}_6") (pintype "bidirectional"))
    )
  )
)
